# mapleCUx_large_350-005.net
KiCad netlist of a schematic drawn in EAGLE
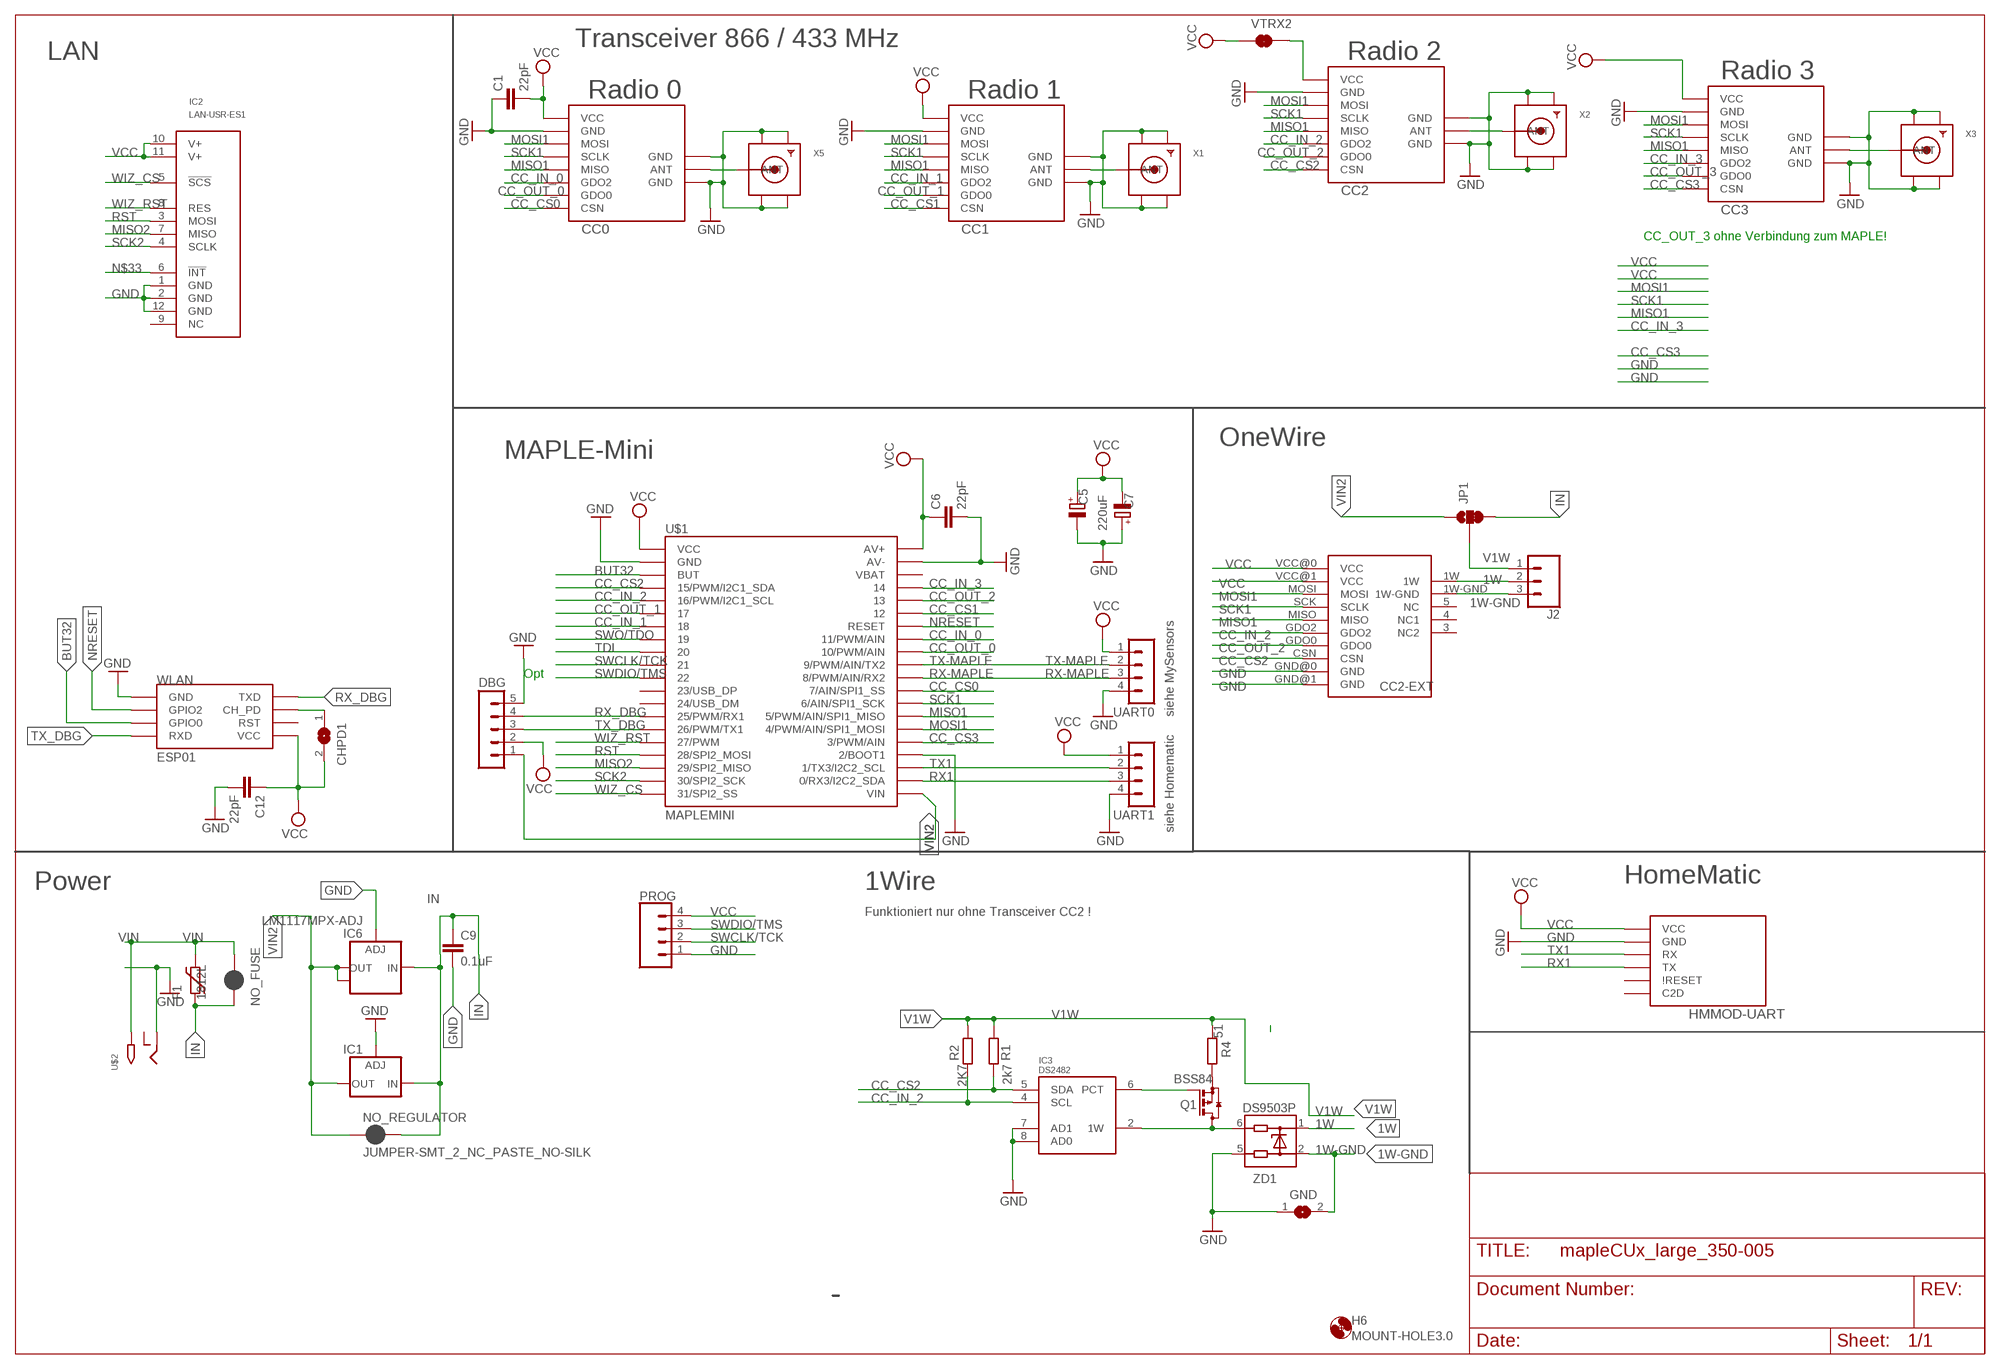
[diagram p0: schematic, sheet 1]

(export (version "E")
  (design (tool "Eeschema 10.0.6"))
  (components
    (comp (ref "C1")
      (value "22pF")
      (footprint "eagle-import:C0805")
      (libsource (lib "eagle-import") (part "C-EUC0805"))
    )
    (comp (ref "C5")
      (value "220uF")
      (footprint "eagle-import:E5-8,5")
      (libsource (lib "eagle-import") (part "CPOL-EUE5-8.5"))
    )
    (comp (ref "C6")
      (value "22pF")
      (footprint "eagle-import:C0805")
      (libsource (lib "eagle-import") (part "C-EUC0805"))
    )
    (comp (ref "C7")
      (value "CPOL-EUSMCE")
      (footprint "eagle-import:SMC_E")
      (libsource (lib "eagle-import") (part "rcl_334_CPOL-EUSMCE"))
    )
    (comp (ref "C9")
      (value "0.1uF")
      (footprint "eagle-import:C1206")
      (libsource (lib "eagle-import") (part "C-EUC1206"))
    )
    (comp (ref "C12")
      (value "22pF")
      (footprint "eagle-import:C0805")
      (libsource (lib "eagle-import") (part "C-EUC0805"))
    )
    (comp (ref "CC0")
      (value "CC1101")
      (footprint "eagle-import:CC1101_MODULE1_SMD")
      (libsource (lib "eagle-import") (part "CC1101_MODULE1SMD"))
    )
    (comp (ref "CC1")
      (value "CC1101_MODULE1SMD")
      (footprint "eagle-import:CC1101_MODULE1_SMD")
      (libsource (lib "eagle-import") (part "CC1101_MODULE1SMD"))
    )
    (comp (ref "CC2")
      (value "CC1101_MODULE1SMD")
      (footprint "eagle-import:CC1101_MODULE1_SMD")
      (libsource (lib "eagle-import") (part "CC1101_MODULE1SMD"))
    )
    (comp (ref "CC2-EXT")
      (value "ONEWIRE-MODULE")
      (footprint "eagle-import:ONEWIRE_CC1101_MODULE3_DIL")
      (libsource (lib "eagle-import") (part "ONEWIRE-MODULE"))
    )
    (comp (ref "CC3")
      (value "CC1101_MODULE1SMD")
      (footprint "eagle-import:CC1101_MODULE1_SMD")
      (libsource (lib "eagle-import") (part "CC1101_MODULE1SMD"))
    )
    (comp (ref "CHPD1")
      (value "SJ")
      (footprint "eagle-import:SJ")
      (libsource (lib "eagle-import") (part "SJ"))
    )
    (comp (ref "DBG")
      (value "MA05-1")
      (footprint "eagle-import:MA05-1")
      (libsource (lib "eagle-import") (part "MA05-1"))
    )
    (comp (ref "F1")
      (value "1812L")
      (footprint "eagle-import:1812L")
      (libsource (lib "eagle-import") (part "1812L"))
    )
    (comp (ref "GND") (value "SJ") (footprint "eagle-import:SJ") (libsource (lib "eagle-import") (part "SJ")))
    (comp (ref "H6")
      (value "MOUNT-HOLE3.0")
      (footprint "eagle-import:3,0")
      (libsource (lib "eagle-import") (part "MOUNT-HOLE3.0"))
    )
    (comp (ref "HMMOD-UART")
      (value "HM-MOD-UARTDIL")
      (footprint "eagle-import:HM-MOD-UART-DIL")
      (libsource (lib "eagle-import") (part "HM-MOD-UARTDIL"))
    )
    (comp (ref "IC1")
      (value "LD117ADT50TR")
      (footprint "eagle-import:DPACK")
      (libsource (lib "eagle-import") (part "LD117A?DT50TR"))
    )
    (comp (ref "IC2")
      (value "LAN-USR-ES1")
      (footprint "eagle-import:USR-ES1")
      (libsource (lib "eagle-import") (part "LAN-USR-ES1"))
    )
    (comp (ref "IC3")
      (value "DS2482")
      (footprint "eagle-import:SO08")
      (libsource (lib "eagle-import") (part "DS2482-100S"))
    )
    (comp (ref "IC6")
      (value "LM1117MPX-ADJ")
      (footprint "eagle-import:SOT223")
      (libsource (lib "eagle-import") (part "LM1117MPX-ADJ"))
    )
    (comp (ref "J2")
      (value "CONN_03LONGPADS")
      (footprint "eagle-import:1X03_LONGPADS")
      (libsource (lib "eagle-import") (part "CONN_03LONGPADS"))
    )
    (comp (ref "JP1")
      (value "JUMPER-SMT_3_1-NC_TRACE_SILK")
      (footprint "eagle-import:SMT-JUMPER_3_1-NC_TRACE_SILK")
      (libsource (lib "eagle-import") (part "JUMPER-SMT_3_1-NC_TRACE_SILK"))
    )
    (comp (ref "NO_FUSE")
      (value "JUMPER-SMT_2_NC_PASTE_NO-SILK")
      (footprint "eagle-import:SMT-JUMPER_2_NC_PASTE_NO-SILK")
      (libsource (lib "eagle-import") (part "JUMPER-SMT_2_NC_PASTE_NO-SILK"))
    )
    (comp (ref "NO_REGULATOR")
      (value "JUMPER-SMT_2_NC_PASTE_NO-SILK")
      (footprint "eagle-import:SMT-JUMPER_2_NC_PASTE_NO-SILK")
      (libsource (lib "eagle-import") (part "JUMPER-SMT_2_NC_PASTE_NO-SILK"))
    )
    (comp (ref "PROG")
      (value "CONN_04LOCK")
      (footprint "eagle-import:1X04_LOCK")
      (libsource (lib "eagle-import") (part "CONN_04LOCK"))
    )
    (comp (ref "Q1")
      (value "BSS84")
      (footprint "eagle-import:SOT23")
      (libsource (lib "eagle-import") (part "BSS84"))
    )
    (comp (ref "R1")
      (value "2k7")
      (footprint "eagle-import:R0805")
      (libsource (lib "eagle-import") (part "R-EU_R0805"))
    )
    (comp (ref "R2")
      (value "2K7")
      (footprint "eagle-import:R0805")
      (libsource (lib "eagle-import") (part "R-EU_R0805"))
    )
    (comp (ref "R4")
      (value "51")
      (footprint "eagle-import:R0805")
      (libsource (lib "eagle-import") (part "R-EU_R0805"))
    )
    (comp (ref "U$1")
      (value "MAPLEMINI")
      (footprint "eagle-import:20-DIP")
      (libsource (lib "eagle-import") (part "MAPLEMINI"))
    )
    (comp (ref "U$2")
      (value "2.1MMJACKTHM")
      (footprint "eagle-import:PJ-102A")
      (libsource (lib "eagle-import") (part "2.1MMJACKTHM"))
    )
    (comp (ref "UART0")
      (value "MA04-1")
      (footprint "eagle-import:MA04-1")
      (libsource (lib "eagle-import") (part "MA04-1"))
    )
    (comp (ref "UART1")
      (value "MA04-1")
      (footprint "eagle-import:MA04-1")
      (libsource (lib "eagle-import") (part "MA04-1"))
    )
    (comp (ref "VTRX2")
      (value "JUMPER-SMT_2_NC_TRACE_SILK")
      (footprint "eagle-import:SMT-JUMPER_2_NC_TRACE_SILK")
      (libsource (lib "eagle-import") (part "JUMPER-SMT_2_NC_TRACE_SILK"))
    )
    (comp (ref "WLAN")
      (value "ESP01")
      (footprint "eagle-import:ESP01")
      (libsource (lib "eagle-import") (part "ESP01"))
    )
    (comp (ref "X1")
      (value "SMACONNECTOR_EDGE")
      (footprint "eagle-import:SMA_EDGELAUNCH")
      (libsource (lib "eagle-import") (part "SMACONNECTOR_EDGE"))
    )
    (comp (ref "X2")
      (value "SMACONNECTOR_EDGE")
      (footprint "eagle-import:SMA_EDGELAUNCH")
      (libsource (lib "eagle-import") (part "SMACONNECTOR_EDGE"))
    )
    (comp (ref "X3")
      (value "SMACONNECTOR_EDGE")
      (footprint "eagle-import:SMA_EDGELAUNCH")
      (libsource (lib "eagle-import") (part "SMACONNECTOR_EDGE"))
    )
    (comp (ref "X5")
      (value "SMACONNECTOR_EDGE")
      (footprint "eagle-import:SMA_EDGELAUNCH")
      (libsource (lib "eagle-import") (part "SMACONNECTOR_EDGE"))
    )
    (comp (ref "ZD1")
      (value "DS9503P")
      (footprint "eagle-import:TSOC6")
      (libsource (lib "eagle-import") (part "DS9503P"))
    )
  )
  (nets
    (net (code "1") (name "/CC_CS0") (class "Default")
      (node (ref "CC0") (pin "CSN") (pinfunction "CSN_CSN") (pintype "bidirectional"))
      (node (ref "U$1") (pin "29") (pinfunction "7/AIN/SPI1_SS_29") (pintype "bidirectional"))
    )
    (net (code "2") (name "/CC_CS1") (class "Default")
      (node (ref "CC1") (pin "CSN") (pinfunction "CSN_CSN") (pintype "bidirectional"))
      (node (ref "U$1") (pin "35") (pinfunction "12_35") (pintype "bidirectional"))
    )
    (net (code "3") (name "/CC_CS2") (class "Default")
      (node (ref "CC2") (pin "CSN") (pinfunction "CSN_CSN") (pintype "bidirectional"))
      (node (ref "CC2-EXT") (pin "CSN") (pinfunction "CSN_CSN") (pintype "bidirectional"))
      (node (ref "IC3") (pin "5") (pinfunction "SDA_5") (pintype "bidirectional"))
      (node (ref "R1") (pin "2") (pinfunction "2_2") (pintype "passive"))
      (node (ref "U$1") (pin "4") (pinfunction "15/PWM/I2C1_SDA_4") (pintype "bidirectional"))
    )
    (net (code "4") (name "/CC_CS3") (class "Default")
      (node (ref "CC3") (pin "CSN") (pinfunction "CSN_CSN") (pintype "bidirectional"))
      (node (ref "U$1") (pin "25") (pinfunction "3/PWM/AIN_25") (pintype "bidirectional"))
    )
    (net (code "5") (name "/CC_IN_0") (class "Default")
      (node (ref "CC0") (pin "GDO2") (pinfunction "GDO2_GDO2") (pintype "bidirectional"))
      (node (ref "U$1") (pin "33") (pinfunction "11/PWM/AIN_33") (pintype "bidirectional"))
    )
    (net (code "6") (name "/CC_IN_1") (class "Default")
      (node (ref "CC1") (pin "GDO2") (pinfunction "GDO2_GDO2") (pintype "bidirectional"))
      (node (ref "U$1") (pin "7") (pinfunction "18_7") (pintype "bidirectional"))
    )
    (net (code "7") (name "/CC_IN_2") (class "Default")
      (node (ref "CC2") (pin "GDO2") (pinfunction "GDO2_GDO2") (pintype "bidirectional"))
      (node (ref "CC2-EXT") (pin "GDO2") (pinfunction "GDO2_GDO2") (pintype "bidirectional"))
      (node (ref "IC3") (pin "4") (pinfunction "SCL_4") (pintype "input"))
      (node (ref "R2") (pin "2") (pinfunction "2_2") (pintype "passive"))
      (node (ref "U$1") (pin "5") (pinfunction "16/PWM/I2C1_SCL_5") (pintype "bidirectional"))
    )
    (net (code "8") (name "/CC_IN_3") (class "Default")
      (node (ref "CC3") (pin "GDO2") (pinfunction "GDO2_GDO2") (pintype "bidirectional"))
      (node (ref "U$1") (pin "37") (pinfunction "14_37") (pintype "bidirectional"))
    )
    (net (code "9") (name "/CC_OUT_0") (class "Default")
      (node (ref "CC0") (pin "GDO0") (pinfunction "GDO0_GDO0") (pintype "bidirectional"))
      (node (ref "U$1") (pin "32") (pinfunction "10/PWM/AIN_32") (pintype "bidirectional"))
    )
    (net (code "10") (name "/CC_OUT_1") (class "Default")
      (node (ref "CC1") (pin "GDO0") (pinfunction "GDO0_GDO0") (pintype "bidirectional"))
      (node (ref "U$1") (pin "6") (pinfunction "17_6") (pintype "bidirectional"))
    )
    (net (code "11") (name "/CC_OUT_2") (class "Default")
      (node (ref "CC2") (pin "GDO0") (pinfunction "GDO0_GDO0") (pintype "bidirectional"))
      (node (ref "CC2-EXT") (pin "GDO0") (pinfunction "GDO0_GDO0") (pintype "bidirectional"))
      (node (ref "U$1") (pin "36") (pinfunction "13_36") (pintype "bidirectional"))
    )
    (net (code "12") (name "/CC_OUT_3") (class "Default")
      (node (ref "CC3") (pin "GDO0") (pinfunction "GDO0_GDO0") (pintype "bidirectional"))
    )
    (net (code "13") (name "/MISO1") (class "Default")
      (node (ref "CC0") (pin "MISO") (pinfunction "MISO_MISO") (pintype "bidirectional"))
      (node (ref "CC1") (pin "MISO") (pinfunction "MISO_MISO") (pintype "bidirectional"))
      (node (ref "CC2") (pin "MISO") (pinfunction "MISO_MISO") (pintype "bidirectional"))
      (node (ref "CC2-EXT") (pin "MISO") (pinfunction "MISO_MISO") (pintype "bidirectional"))
      (node (ref "CC3") (pin "MISO") (pinfunction "MISO_MISO") (pintype "bidirectional"))
      (node (ref "U$1") (pin "27") (pinfunction "5/PWM/AIN/SPI1_MISO_27") (pintype "bidirectional"))
    )
    (net (code "14") (name "/MISO2") (class "Default")
      (node (ref "IC2") (pin "7") (pinfunction "MISO_7") (pintype "bidirectional"))
      (node (ref "U$1") (pin "18") (pinfunction "29/SPI2_MISO_18") (pintype "bidirectional"))
    )
    (net (code "15") (name "/MOSI1") (class "Default")
      (node (ref "CC0") (pin "MOSI") (pinfunction "MOSI_MOSI") (pintype "bidirectional"))
      (node (ref "CC1") (pin "MOSI") (pinfunction "MOSI_MOSI") (pintype "bidirectional"))
      (node (ref "CC2") (pin "MOSI") (pinfunction "MOSI_MOSI") (pintype "bidirectional"))
      (node (ref "CC2-EXT") (pin "MOSI") (pinfunction "MOSI_MOSI") (pintype "bidirectional"))
      (node (ref "CC3") (pin "MOSI") (pinfunction "MOSI_MOSI") (pintype "bidirectional"))
      (node (ref "U$1") (pin "26") (pinfunction "4/PWM/AIN/SPI1_MOSI_26") (pintype "bidirectional"))
    )
    (net (code "16") (name "/N$33") (class "Default")
      (node (ref "IC2") (pin "6") (pinfunction "~{INT}_6") (pintype "output"))
    )
    (net (code "17") (name "/RST") (class "Default")
      (node (ref "IC2") (pin "3") (pinfunction "MOSI_3") (pintype "bidirectional"))
      (node (ref "U$1") (pin "17") (pinfunction "28/SPI2_MOSI_17") (pintype "bidirectional"))
    )
    (net (code "18") (name "/RX-MAPLE") (class "Default")
      (node (ref "U$1") (pin "30") (pinfunction "8/PWM/AIN/RX2_30") (pintype "bidirectional"))
      (node (ref "UART0") (pin "3") (pinfunction "3_3") (pintype "passive"))
    )
    (net (code "19") (name "/RX1") (class "Default")
      (node (ref "HMMOD-UART") (pin "5") (pinfunction "TX_5") (pintype "bidirectional"))
      (node (ref "U$1") (pin "22") (pinfunction "0/RX3/I2C2_SDA_22") (pintype "bidirectional"))
      (node (ref "UART1") (pin "3") (pinfunction "3_3") (pintype "passive"))
    )
    (net (code "20") (name "/SCK1") (class "Default")
      (node (ref "CC0") (pin "SCLK") (pinfunction "SCLK_SCLK") (pintype "bidirectional"))
      (node (ref "CC1") (pin "SCLK") (pinfunction "SCLK_SCLK") (pintype "bidirectional"))
      (node (ref "CC2") (pin "SCLK") (pinfunction "SCLK_SCLK") (pintype "bidirectional"))
      (node (ref "CC2-EXT") (pin "SCK") (pinfunction "SCLK_SCK") (pintype "bidirectional"))
      (node (ref "CC3") (pin "SCLK") (pinfunction "SCLK_SCLK") (pintype "bidirectional"))
      (node (ref "U$1") (pin "28") (pinfunction "6/AIN/SPI1_SCK_28") (pintype "bidirectional"))
    )
    (net (code "21") (name "/SCK2") (class "Default")
      (node (ref "IC2") (pin "4") (pinfunction "SCLK_4") (pintype "input"))
      (node (ref "U$1") (pin "19") (pinfunction "30/SPI2_SCK_19") (pintype "bidirectional"))
    )
    (net (code "22") (name "/SWCLK{slash}TCK") (class "Default")
      (node (ref "PROG") (pin "2") (pinfunction "2_2") (pintype "passive"))
      (node (ref "U$1") (pin "10") (pinfunction "21_10") (pintype "bidirectional"))
    )
    (net (code "23") (name "/SWDIO{slash}TMS") (class "Default")
      (node (ref "PROG") (pin "3") (pinfunction "3_3") (pintype "passive"))
      (node (ref "U$1") (pin "11") (pinfunction "22_11") (pintype "bidirectional"))
    )
    (net (code "24") (name "/SWO{slash}TDO") (class "Default")
      (node (ref "U$1") (pin "8") (pinfunction "19_8") (pintype "bidirectional"))
    )
    (net (code "25") (name "/TDI") (class "Default")
      (node (ref "U$1") (pin "9") (pinfunction "20_9") (pintype "bidirectional"))
    )
    (net (code "26") (name "/TX-MAPLE") (class "Default")
      (node (ref "U$1") (pin "31") (pinfunction "9/PWM/AIN/TX2_31") (pintype "bidirectional"))
      (node (ref "UART0") (pin "2") (pinfunction "2_2") (pintype "passive"))
    )
    (net (code "27") (name "/TX1") (class "Default")
      (node (ref "HMMOD-UART") (pin "6") (pinfunction "RX_6") (pintype "bidirectional"))
      (node (ref "U$1") (pin "23") (pinfunction "1/TX3/I2C2_SCL_23") (pintype "bidirectional"))
      (node (ref "UART1") (pin "2") (pinfunction "2_2") (pintype "passive"))
    )
    (net (code "28") (name "/VIN") (class "Default")
      (node (ref "F1") (pin "P$2") (pinfunction "2_P$2") (pintype "passive"))
      (node (ref "NO_FUSE") (pin "2") (pinfunction "2_2") (pintype "passive"))
      (node (ref "U$2") (pin "TIP") (pinfunction "TIP_TIP") (pintype "bidirectional"))
    )
    (net (code "29") (name "/WIZ_CS") (class "Default")
      (node (ref "IC2") (pin "5") (pinfunction "~{SCS}_5") (pintype "input"))
      (node (ref "U$1") (pin "20") (pinfunction "31/SPI2_SS_20") (pintype "bidirectional"))
    )
    (net (code "30") (name "/WIZ_RST") (class "Default")
      (node (ref "IC2") (pin "8") (pinfunction "RES_8") (pintype "input"))
      (node (ref "U$1") (pin "16") (pinfunction "27/PWM_16") (pintype "bidirectional"))
    )
    (net (code "31") (name "1W") (class "Default")
      (node (ref "CC2-EXT") (pin "1W") (pinfunction "1W_1W") (pintype "bidirectional"))
      (node (ref "J2") (pin "2") (pinfunction "2_2") (pintype "passive"))
      (node (ref "ZD1") (pin "1") (pinfunction "P$1_1") (pintype "passive"))
    )
    (net (code "32") (name "1W-GND") (class "Default")
      (node (ref "CC2-EXT") (pin "1W-GND") (pinfunction "1W-GND_1W-GND") (pintype "bidirectional"))
      (node (ref "GND") (pin "2") (pinfunction "2_2") (pintype "passive"))
      (node (ref "J2") (pin "3") (pinfunction "3_3") (pintype "passive"))
      (node (ref "ZD1") (pin "2") (pinfunction "P$2_2") (pintype "passive"))
    )
    (net (code "33") (name "BUT32") (class "Default")
      (node (ref "U$1") (pin "3") (pinfunction "BUT_3") (pintype "bidirectional"))
      (node (ref "WLAN") (pin "GPIO0") (pinfunction "GPIO0_GPIO0") (pintype "bidirectional"))
    )
    (net (code "34") (name "GND") (class "Default")
      (node (ref "C1") (pin "1") (pinfunction "1_1") (pintype "passive"))
      (node (ref "C12") (pin "2") (pinfunction "2_2") (pintype "passive"))
      (node (ref "C5") (pin "-") (pinfunction "-_-") (pintype "passive"))
      (node (ref "C6") (pin "2") (pinfunction "2_2") (pintype "passive"))
      (node (ref "C7") (pin "+") (pinfunction "+_+") (pintype "passive"))
      (node (ref "C9") (pin "2") (pinfunction "2_2") (pintype "passive"))
      (node (ref "CC0") (pin "GND@0") (pinfunction "GND_GND@0") (pintype "power_in"))
      (node (ref "CC0") (pin "GND@1") (pinfunction "GND_GND@1") (pintype "power_in"))
      (node (ref "CC0") (pin "GND@2") (pinfunction "GND_GND@2") (pintype "power_in"))
      (node (ref "CC1") (pin "GND@0") (pinfunction "GND_GND@0") (pintype "power_in"))
      (node (ref "CC1") (pin "GND@1") (pinfunction "GND_GND@1") (pintype "power_in"))
      (node (ref "CC1") (pin "GND@2") (pinfunction "GND_GND@2") (pintype "power_in"))
      (node (ref "CC2") (pin "GND@0") (pinfunction "GND_GND@0") (pintype "power_in"))
      (node (ref "CC2") (pin "GND@1") (pinfunction "GND_GND@1") (pintype "power_in"))
      (node (ref "CC2") (pin "GND@2") (pinfunction "GND_GND@2") (pintype "power_in"))
      (node (ref "CC2-EXT") (pin "GND@0") (pinfunction "GND_GND@0") (pintype "power_in"))
      (node (ref "CC2-EXT") (pin "GND@1") (pinfunction "GND_GND@1") (pintype "power_in"))
      (node (ref "CC3") (pin "GND@0") (pinfunction "GND_GND@0") (pintype "power_in"))
      (node (ref "CC3") (pin "GND@1") (pinfunction "GND_GND@1") (pintype "power_in"))
      (node (ref "CC3") (pin "GND@2") (pinfunction "GND_GND@2") (pintype "power_in"))
      (node (ref "DBG") (pin "5") (pinfunction "5_5") (pintype "passive"))
      (node (ref "GND") (pin "1") (pinfunction "1_1") (pintype "passive"))
      (node (ref "HMMOD-UART") (pin "2") (pinfunction "GND_2") (pintype "power_in"))
      (node (ref "IC1") (pin "1") (pinfunction "ADJ_1") (pintype "input"))
      (node (ref "IC2") (pin "1") (pinfunction "GND_1") (pintype "power_in"))
      (node (ref "IC2") (pin "12") (pinfunction "GND_12") (pintype "power_in"))
      (node (ref "IC2") (pin "2") (pinfunction "GND_2") (pintype "power_in"))
      (node (ref "IC3") (pin "7") (pinfunction "AD1_7") (pintype "input"))
      (node (ref "IC3") (pin "8") (pinfunction "AD0_8") (pintype "input"))
      (node (ref "IC6") (pin "1") (pinfunction "ADJ_1") (pintype "input"))
      (node (ref "PROG") (pin "1") (pinfunction "1_1") (pintype "passive"))
      (node (ref "U$1") (pin "2") (pinfunction "GND_2") (pintype "bidirectional"))
      (node (ref "U$1") (pin "24") (pinfunction "2/BOOT1_24") (pintype "bidirectional"))
      (node (ref "U$1") (pin "39") (pinfunction "AV-_39") (pintype "bidirectional"))
      (node (ref "U$2") (pin "RING") (pinfunction "RING_RING") (pintype "bidirectional"))
      (node (ref "UART0") (pin "4") (pinfunction "4_4") (pintype "passive"))
      (node (ref "UART1") (pin "4") (pinfunction "4_4") (pintype "passive"))
      (node (ref "WLAN") (pin "GND") (pinfunction "GND_GND") (pintype "bidirectional"))
      (node (ref "X1") (pin "GND@1") (pinfunction "GND4_GND@1") (pintype "power_in"))
      (node (ref "X1") (pin "GND@2") (pinfunction "GND3_GND@2") (pintype "power_in"))
      (node (ref "X1") (pin "GND@3") (pinfunction "GND2_GND@3") (pintype "power_in"))
      (node (ref "X1") (pin "GND@4") (pinfunction "GND1_GND@4") (pintype "power_in"))
      (node (ref "X2") (pin "GND@1") (pinfunction "GND4_GND@1") (pintype "power_in"))
      (node (ref "X2") (pin "GND@2") (pinfunction "GND3_GND@2") (pintype "power_in"))
      (node (ref "X2") (pin "GND@3") (pinfunction "GND2_GND@3") (pintype "power_in"))
      (node (ref "X2") (pin "GND@4") (pinfunction "GND1_GND@4") (pintype "power_in"))
      (node (ref "X3") (pin "GND@1") (pinfunction "GND4_GND@1") (pintype "power_in"))
      (node (ref "X3") (pin "GND@2") (pinfunction "GND3_GND@2") (pintype "power_in"))
      (node (ref "X3") (pin "GND@3") (pinfunction "GND2_GND@3") (pintype "power_in"))
      (node (ref "X3") (pin "GND@4") (pinfunction "GND1_GND@4") (pintype "power_in"))
      (node (ref "X5") (pin "GND@1") (pinfunction "GND4_GND@1") (pintype "power_in"))
      (node (ref "X5") (pin "GND@2") (pinfunction "GND3_GND@2") (pintype "power_in"))
      (node (ref "X5") (pin "GND@3") (pinfunction "GND2_GND@3") (pintype "power_in"))
      (node (ref "X5") (pin "GND@4") (pinfunction "GND1_GND@4") (pintype "power_in"))
      (node (ref "ZD1") (pin "5") (pinfunction "P$3_5") (pintype "passive"))
    )
    (net (code "35") (name "IN") (class "Default")
      (node (ref "C9") (pin "1") (pinfunction "1_1") (pintype "passive"))
      (node (ref "F1") (pin "P$1") (pinfunction "1_P$1") (pintype "passive"))
      (node (ref "IC1") (pin "3") (pinfunction "IN_3") (pintype "input"))
      (node (ref "IC6") (pin "3") (pinfunction "IN_3") (pintype "input"))
      (node (ref "JP1") (pin "3") (pinfunction "3_3") (pintype "passive"))
      (node (ref "NO_FUSE") (pin "1") (pinfunction "1_1") (pintype "passive"))
      (node (ref "NO_REGULATOR") (pin "2") (pinfunction "2_2") (pintype "passive"))
    )
    (net (code "36") (name "NRESET") (class "Default")
      (node (ref "U$1") (pin "34") (pinfunction "RESET_34") (pintype "bidirectional"))
      (node (ref "WLAN") (pin "GPIO2") (pinfunction "GPIO2_GPIO2") (pintype "bidirectional"))
    )
    (net (code "37") (name "Net-(CC2-PadVCC)") (class "Default")
      (node (ref "CC2") (pin "VCC") (pinfunction "VCC_VCC") (pintype "power_in"))
      (node (ref "VTRX2") (pin "2") (pinfunction "2_2") (pintype "passive"))
    )
    (net (code "38") (name "Net-(CHPD1-Pad1)") (class "Default")
      (node (ref "CHPD1") (pin "1") (pinfunction "1_1") (pintype "passive"))
      (node (ref "WLAN") (pin "CH_PD") (pinfunction "CH_PD_CH_PD") (pintype "bidirectional"))
    )
    (net (code "39") (name "Net-(IC3A-1W)") (class "Default")
      (node (ref "IC3") (pin "2") (pinfunction "1W_2") (pintype "open_collector"))
      (node (ref "Q1") (pin "3") (pinfunction "D_3") (pintype "passive"))
      (node (ref "ZD1") (pin "6") (pinfunction "P$4_6") (pintype "passive"))
    )
    (net (code "40") (name "Net-(IC3A-PCT)") (class "Default")
      (node (ref "IC3") (pin "6") (pinfunction "PCT_6") (pintype "output"))
      (node (ref "Q1") (pin "1") (pinfunction "G_1") (pintype "passive"))
    )
    (net (code "41") (name "Net-(Q1-S)") (class "Default")
      (node (ref "Q1") (pin "2") (pinfunction "S_2") (pintype "passive"))
      (node (ref "R4") (pin "1") (pinfunction "1_1") (pintype "passive"))
    )
    (net (code "42") (name "Net-(X1-ANT)") (class "Default")
      (node (ref "CC1") (pin "ANT") (pinfunction "ANT_ANT") (pintype "output"))
      (node (ref "X1") (pin "P") (pinfunction "ANT_P") (pintype "bidirectional"))
    )
    (net (code "43") (name "Net-(X2-ANT)") (class "Default")
      (node (ref "CC2") (pin "ANT") (pinfunction "ANT_ANT") (pintype "output"))
      (node (ref "X2") (pin "P") (pinfunction "ANT_P") (pintype "bidirectional"))
    )
    (net (code "44") (name "Net-(X3-ANT)") (class "Default")
      (node (ref "CC3") (pin "ANT") (pinfunction "ANT_ANT") (pintype "output"))
      (node (ref "X3") (pin "P") (pinfunction "ANT_P") (pintype "bidirectional"))
    )
    (net (code "45") (name "Net-(X5-ANT)") (class "Default")
      (node (ref "CC0") (pin "ANT") (pinfunction "ANT_ANT") (pintype "output"))
      (node (ref "X5") (pin "P") (pinfunction "ANT_P") (pintype "bidirectional"))
    )
    (net (code "46") (name "RX_DBG") (class "Default")
      (node (ref "DBG") (pin "4") (pinfunction "4_4") (pintype "passive"))
      (node (ref "U$1") (pin "14") (pinfunction "25/PWM/RX1_14") (pintype "bidirectional"))
      (node (ref "WLAN") (pin "TX") (pinfunction "TXD_TX") (pintype "bidirectional"))
    )
    (net (code "47") (name "TX_DBG") (class "Default")
      (node (ref "DBG") (pin "3") (pinfunction "3_3") (pintype "passive"))
      (node (ref "U$1") (pin "15") (pinfunction "26/PWM/TX1_15") (pintype "bidirectional"))
      (node (ref "WLAN") (pin "RX") (pinfunction "RXD_RX") (pintype "bidirectional"))
    )
    (net (code "48") (name "V1W") (class "Default")
      (node (ref "J2") (pin "1") (pinfunction "1_1") (pintype "passive"))
      (node (ref "JP1") (pin "2") (pinfunction "2_2") (pintype "passive"))
      (node (ref "R1") (pin "1") (pinfunction "1_1") (pintype "passive"))
      (node (ref "R2") (pin "1") (pinfunction "1_1") (pintype "passive"))
      (node (ref "R4") (pin "2") (pinfunction "2_2") (pintype "passive"))
    )
    (net (code "49") (name "VCC") (class "Default")
      (node (ref "C1") (pin "2") (pinfunction "2_2") (pintype "passive"))
      (node (ref "C12") (pin "1") (pinfunction "1_1") (pintype "passive"))
      (node (ref "C5") (pin "+") (pinfunction "+_+") (pintype "passive"))
      (node (ref "C6") (pin "1") (pinfunction "1_1") (pintype "passive"))
      (node (ref "C7") (pin "-") (pinfunction "-_-") (pintype "passive"))
      (node (ref "CC0") (pin "VCC") (pinfunction "VCC_VCC") (pintype "power_in"))
      (node (ref "CC1") (pin "VCC") (pinfunction "VCC_VCC") (pintype "power_in"))
      (node (ref "CC2-EXT") (pin "VCC@0") (pinfunction "VCC_VCC@0") (pintype "power_in"))
      (node (ref "CC2-EXT") (pin "VCC@1") (pinfunction "VCC_VCC@1") (pintype "power_in"))
      (node (ref "CC3") (pin "VCC") (pinfunction "VCC_VCC") (pintype "power_in"))
      (node (ref "CHPD1") (pin "2") (pinfunction "2_2") (pintype "passive"))
      (node (ref "DBG") (pin "2") (pinfunction "2_2") (pintype "passive"))
      (node (ref "HMMOD-UART") (pin "1") (pinfunction "VCC_1") (pintype "power_in"))
      (node (ref "IC2") (pin "10") (pinfunction "V+_10") (pintype "power_in"))
      (node (ref "IC2") (pin "11") (pinfunction "V+_11") (pintype "power_in"))
      (node (ref "PROG") (pin "4") (pinfunction "4_4") (pintype "passive"))
      (node (ref "U$1") (pin "1") (pinfunction "VCC_1") (pintype "bidirectional"))
      (node (ref "U$1") (pin "40") (pinfunction "AV+_40") (pintype "bidirectional"))
      (node (ref "UART0") (pin "1") (pinfunction "1_1") (pintype "passive"))
      (node (ref "UART1") (pin "1") (pinfunction "1_1") (pintype "passive"))
      (node (ref "VTRX2") (pin "1") (pinfunction "1_1") (pintype "passive"))
      (node (ref "WLAN") (pin "VCC") (pinfunction "VCC_VCC") (pintype "bidirectional"))
    )
    (net (code "50") (name "VIN2") (class "Default")
      (node (ref "DBG") (pin "1") (pinfunction "1_1") (pintype "passive"))
      (node (ref "IC1") (pin "4") (pinfunction "OUT_4") (pintype "passive"))
      (node (ref "IC6") (pin "2") (pinfunction "OUT_2") (pintype "passive"))
      (node (ref "IC6") (pin "TAB") (pinfunction "OUT1_TAB") (pintype "passive"))
      (node (ref "JP1") (pin "1") (pinfunction "1_1") (pintype "passive"))
      (node (ref "NO_REGULATOR") (pin "1") (pinfunction "1_1") (pintype "passive"))
      (node (ref "U$1") (pin "21") (pinfunction "VIN_21") (pintype "bidirectional"))
    )
    (net (code "51") (name "unconnected-(CC2-EXT-NC-Pad5)") (class "Default")
      (node (ref "CC2-EXT") (pin "5") (pinfunction "NC_5") (pintype "bidirectional"))
    )
    (net (code "52") (name "unconnected-(CC2-EXT-NC1-Pad4)") (class "Default")
      (node (ref "CC2-EXT") (pin "4") (pinfunction "NC1_4") (pintype "bidirectional"))
    )
    (net (code "53") (name "unconnected-(CC2-EXT-NC2-Pad3)") (class "Default")
      (node (ref "CC2-EXT") (pin "3") (pinfunction "NC2_3") (pintype "bidirectional"))
    )
    (net (code "54") (name "unconnected-(HMMOD-UART-C2D-Pad3)") (class "Default")
      (node (ref "HMMOD-UART") (pin "3") (pinfunction "C2D_3") (pintype "bidirectional"))
    )
    (net (code "55") (name "unconnected-(HMMOD-UART-\\~{RESET}-Pad4)") (class "Default")
      (node (ref "HMMOD-UART") (pin "4") (pinfunction "\\~{RESET}_4") (pintype "bidirectional"))
    )
    (net (code "56") (name "unconnected-(IC2-NC-Pad9)") (class "Default")
      (node (ref "IC2") (pin "9") (pinfunction "NC_9") (pintype "no_connect"))
    )
    (net (code "57") (name "unconnected-(U$1-23{slash}USB_DP-Pad12)") (class "Default")
      (node (ref "U$1") (pin "12") (pinfunction "23/USB_DP_12") (pintype "bidirectional"))
    )
    (net (code "58") (name "unconnected-(U$1-24{slash}USB_DM-Pad13)") (class "Default")
      (node (ref "U$1") (pin "13") (pinfunction "24/USB_DM_13") (pintype "bidirectional"))
    )
    (net (code "59") (name "unconnected-(U$1-VBAT-Pad38)") (class "Default")
      (node (ref "U$1") (pin "38") (pinfunction "VBAT_38") (pintype "bidirectional"))
    )
    (net (code "60") (name "unconnected-(U$2-PadRING_SW)") (class "Default")
      (node (ref "U$2") (pin "RING_SW") (pinfunction "RING_SW_RING_SW") (pintype "bidirectional"))
    )
    (net (code "61") (name "unconnected-(WLAN-PadRST)") (class "Default")
      (node (ref "WLAN") (pin "RST") (pinfunction "RST_RST") (pintype "bidirectional"))
    )
  )
)
